# Versie_3.net
KiCad netlist of a schematic drawn in EAGLE
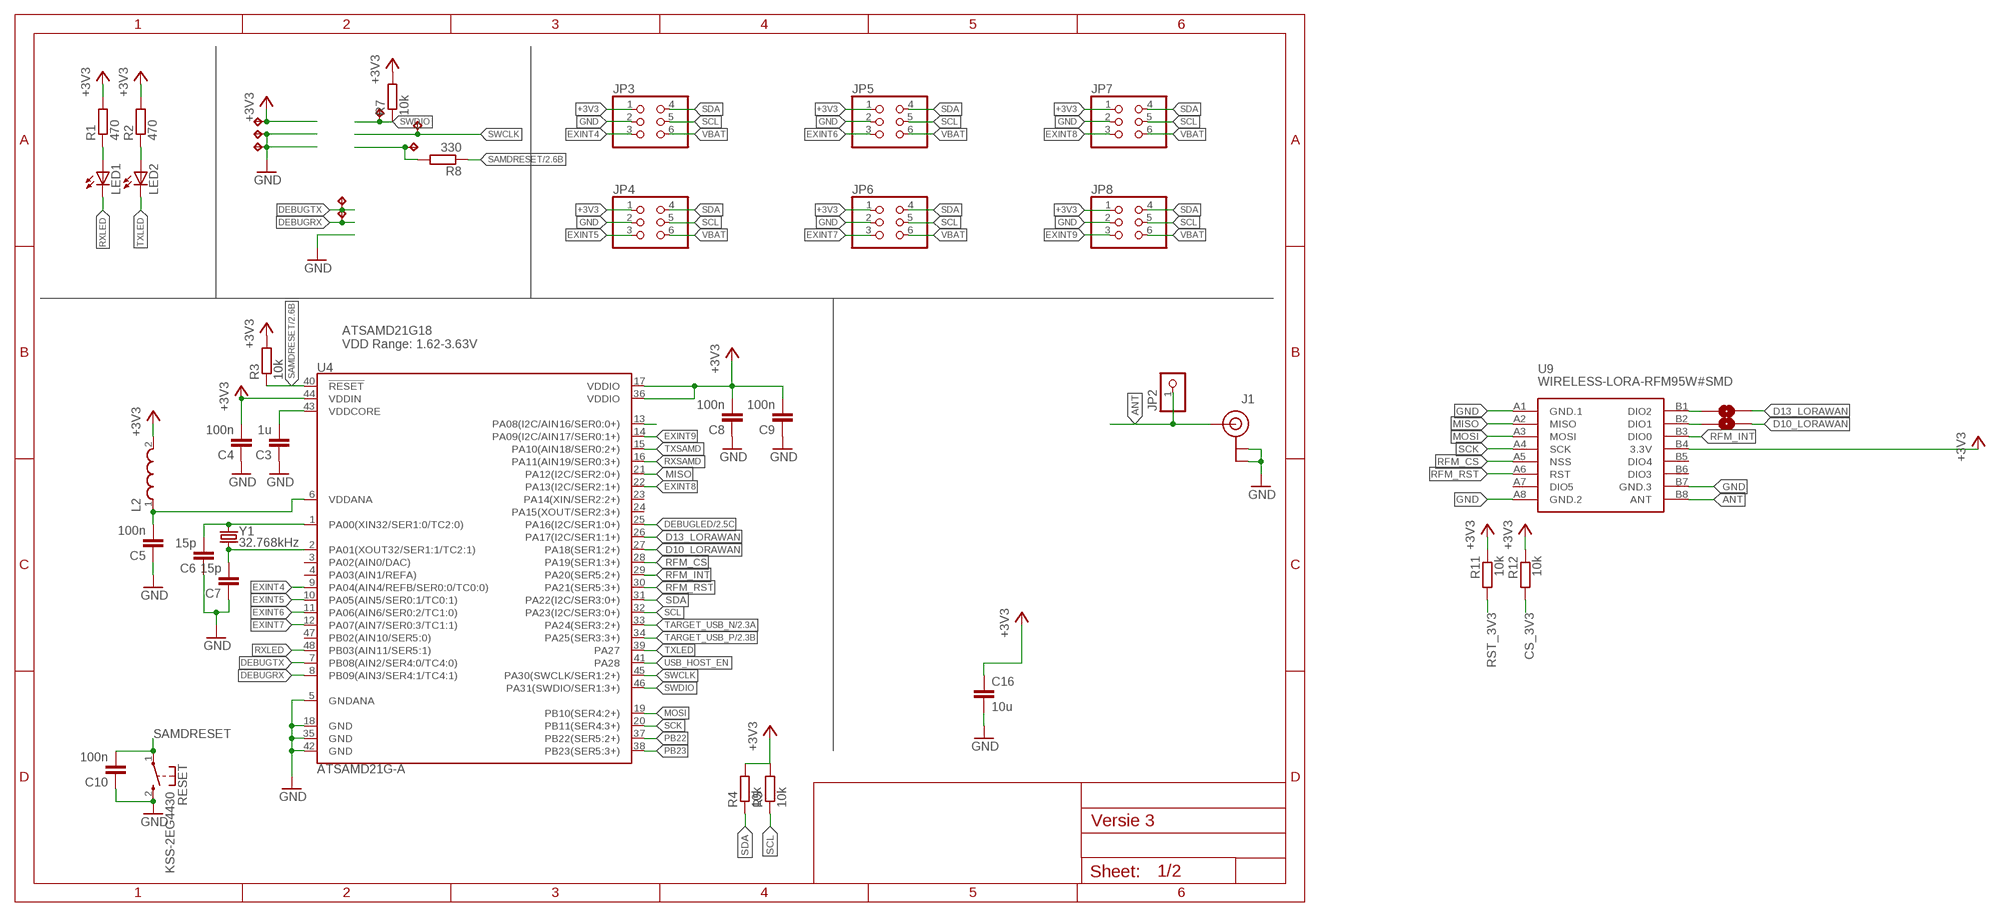
[diagram p0: schematic, sheet 1]
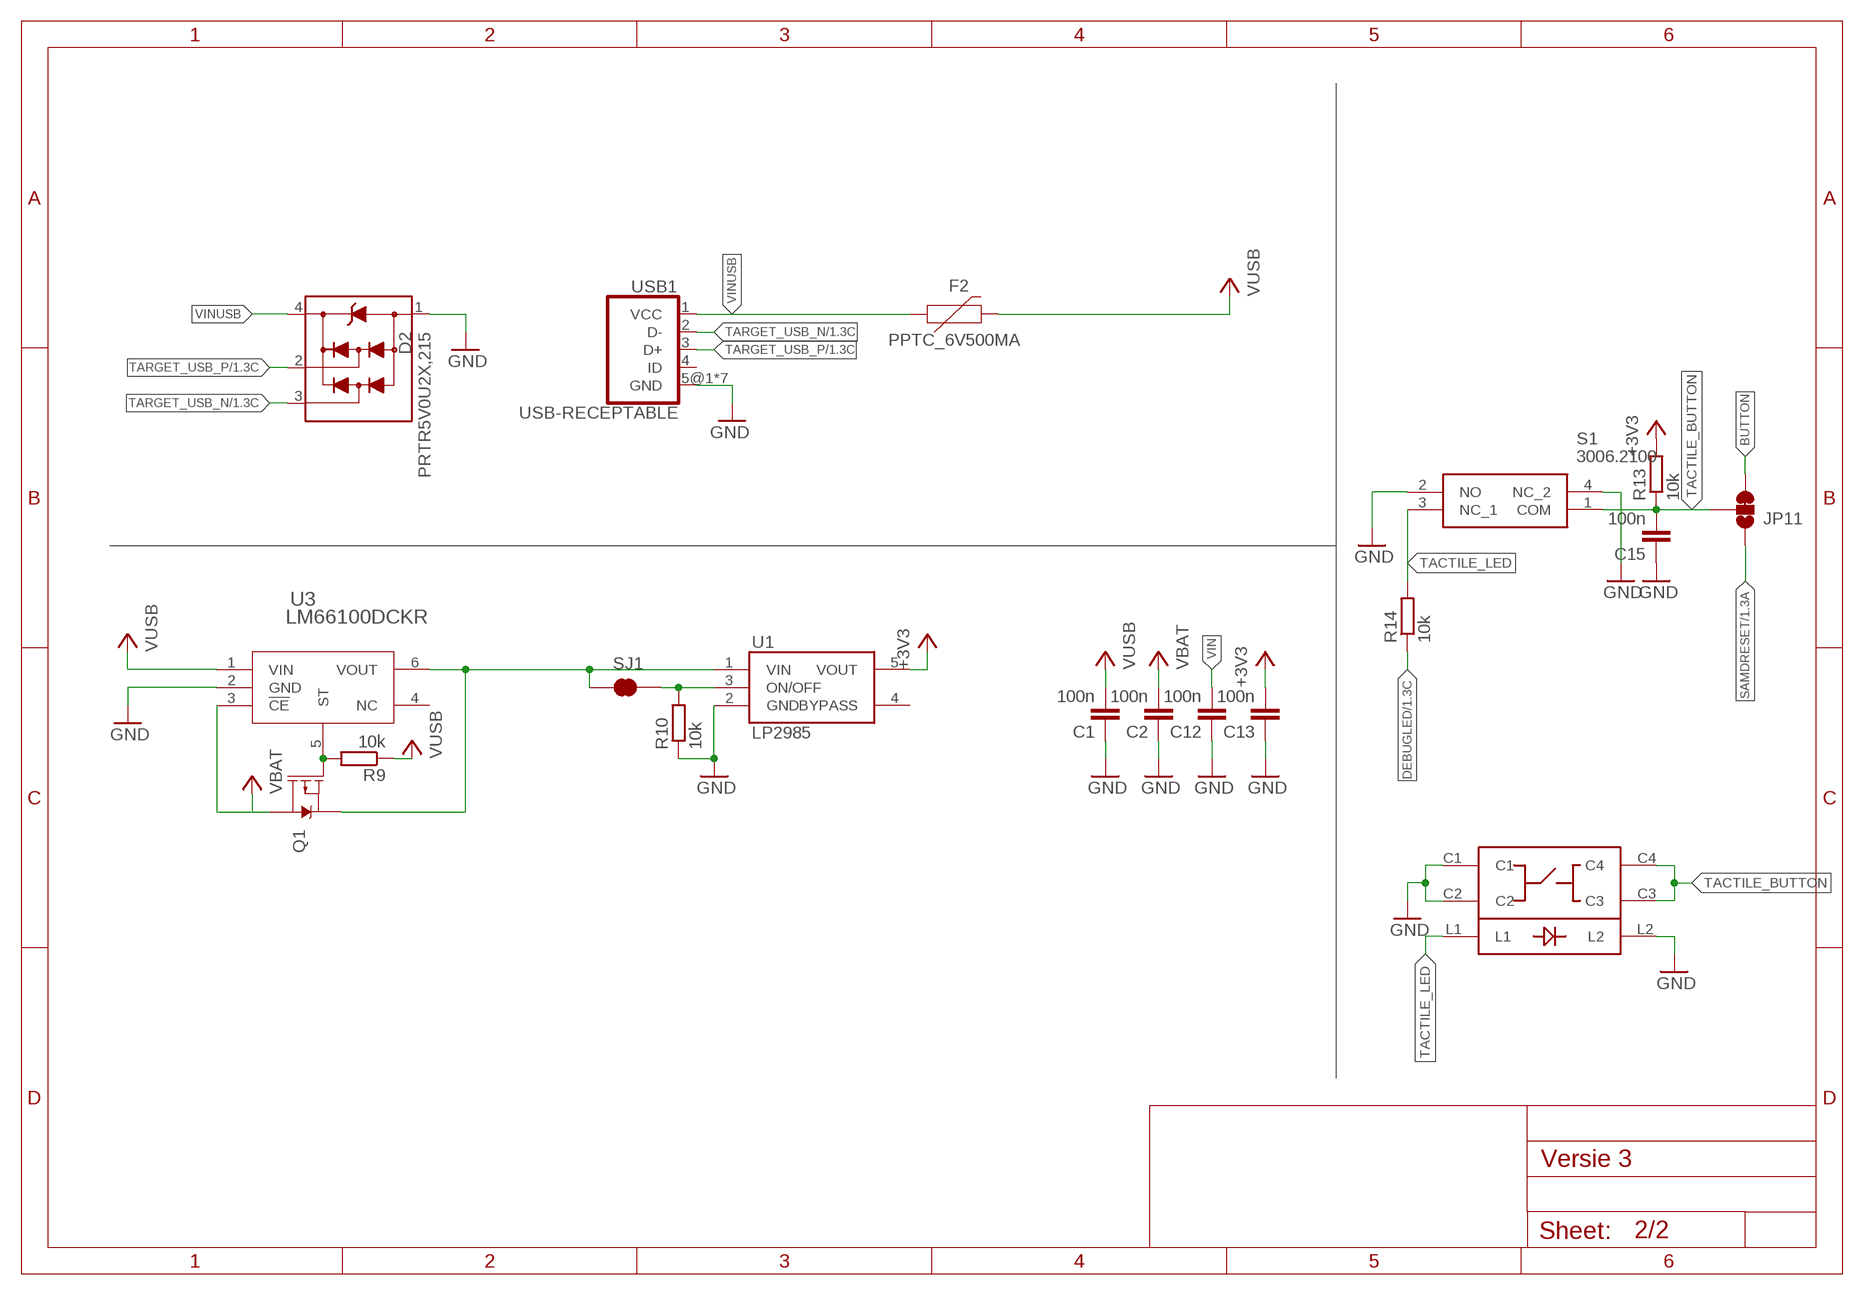
[diagram p1: schematic, sheet 2]

(export (version "E")
  (design (tool "Eeschema 10.0.6"))
  (components
    (comp (ref "C3")
      (value "1u")
      (footprint "eagle-import:C0603")
      (libsource (lib "eagle-import") (part "C-EUC0603"))
    )
    (comp (ref "C4")
      (value "100n")
      (footprint "eagle-import:C0603")
      (libsource (lib "eagle-import") (part "C-EUC0603"))
    )
    (comp (ref "C5")
      (value "100n")
      (footprint "eagle-import:C0603")
      (libsource (lib "eagle-import") (part "C-EUC0603"))
    )
    (comp (ref "C6")
      (value "15p")
      (footprint "eagle-import:C0603")
      (libsource (lib "eagle-import") (part "C-EUC0603"))
    )
    (comp (ref "C7")
      (value "15p")
      (footprint "eagle-import:C0603")
      (libsource (lib "eagle-import") (part "C-EUC0603"))
    )
    (comp (ref "C8")
      (value "100n")
      (footprint "eagle-import:C0603")
      (libsource (lib "eagle-import") (part "C-EUC0603"))
    )
    (comp (ref "C9")
      (value "100n")
      (footprint "eagle-import:C0603")
      (libsource (lib "eagle-import") (part "C-EUC0603"))
    )
    (comp (ref "C10")
      (value "100n")
      (footprint "eagle-import:C0603")
      (libsource (lib "eagle-import") (part "C-EUC0603"))
    )
    (comp (ref "C16")
      (value "10u")
      (footprint "eagle-import:C0603")
      (libsource (lib "eagle-import") (part "C-EUC0603"))
    )
    (comp (ref "J1")
      (value "U.FL")
      (footprint "eagle-import:U.FL")
      (libsource (lib "eagle-import") (part "U.FL"))
    )
    (comp (ref "JP2")
      (value "PINHD-1X1")
      (footprint "eagle-import:1X01")
      (libsource (lib "eagle-import") (part "PINHD-1X1"))
    )
    (comp (ref "JP3")
      (value "PINHD-2X3")
      (footprint "eagle-import:2X03")
      (libsource (lib "eagle-import") (part "PINHD-2X3"))
    )
    (comp (ref "JP4")
      (value "PINHD-2X3")
      (footprint "eagle-import:2X03")
      (libsource (lib "eagle-import") (part "PINHD-2X3"))
    )
    (comp (ref "JP5")
      (value "PINHD-2X3")
      (footprint "eagle-import:2X03")
      (libsource (lib "eagle-import") (part "PINHD-2X3"))
    )
    (comp (ref "JP6")
      (value "PINHD-2X3")
      (footprint "eagle-import:2X03")
      (libsource (lib "eagle-import") (part "PINHD-2X3"))
    )
    (comp (ref "JP7")
      (value "PINHD-2X3")
      (footprint "eagle-import:2X03")
      (libsource (lib "eagle-import") (part "PINHD-2X3"))
    )
    (comp (ref "JP8")
      (value "PINHD-2X3")
      (footprint "eagle-import:2X03")
      (libsource (lib "eagle-import") (part "PINHD-2X3"))
    )
    (comp (ref "JP9")
      (value "JUMPER-SMT_2_NO_NO-SILK")
      (footprint "eagle-import:SMT-JUMPER_2_NO_NO-SILK")
      (libsource (lib "eagle-import") (part "JUMPER-SMT_2_NO_NO-SILK"))
    )
    (comp (ref "JP10")
      (value "JUMPER-SMT_2_NO_NO-SILK")
      (footprint "eagle-import:SMT-JUMPER_2_NO_NO-SILK")
      (libsource (lib "eagle-import") (part "JUMPER-SMT_2_NO_NO-SILK"))
    )
    (comp (ref "L2")
      (value "WE-CBA_0603(WB/HS)")
      (footprint "eagle-import:WE-CBA_0603(W=2.2)")
      (libsource (lib "eagle-import") (part "WE-CBA_0603(WB/HS)"))
    )
    (comp (ref "LED1")
      (value "LEDCHIP-LED0603")
      (footprint "eagle-import:CHIP-LED0603")
      (libsource (lib "eagle-import") (part "LEDCHIP-LED0603"))
    )
    (comp (ref "LED2")
      (value "LEDCHIP-LED0603")
      (footprint "eagle-import:CHIP-LED0603")
      (libsource (lib "eagle-import") (part "LEDCHIP-LED0603"))
    )
    (comp (ref "R1")
      (value "470")
      (footprint "eagle-import:R0603")
      (libsource (lib "eagle-import") (part "R-EU_R0603"))
    )
    (comp (ref "R2")
      (value "470")
      (footprint "eagle-import:R0603")
      (libsource (lib "eagle-import") (part "R-EU_R0603"))
    )
    (comp (ref "R3")
      (value "10k")
      (footprint "eagle-import:R0603")
      (libsource (lib "eagle-import") (part "R-EU_R0603"))
    )
    (comp (ref "R4")
      (value "10k")
      (footprint "eagle-import:R0603")
      (libsource (lib "eagle-import") (part "R-EU_R0603"))
    )
    (comp (ref "R5")
      (value "10k")
      (footprint "eagle-import:R0603")
      (libsource (lib "eagle-import") (part "R-EU_R0603"))
    )
    (comp (ref "R7")
      (value "10k")
      (footprint "eagle-import:R0603")
      (libsource (lib "eagle-import") (part "R-EU_R0603"))
    )
    (comp (ref "R8")
      (value "330")
      (footprint "eagle-import:R0603")
      (libsource (lib "eagle-import") (part "R-EU_R0603"))
    )
    (comp (ref "R11")
      (value "10k")
      (footprint "eagle-import:0204_7")
      (libsource (lib "eagle-import") (part "resistor_R-EU_0204/7"))
    )
    (comp (ref "R12")
      (value "10k")
      (footprint "eagle-import:0204_7")
      (libsource (lib "eagle-import") (part "resistor_R-EU_0204/7"))
    )
    (comp (ref "RESET")
      (value "KSS-2EG4430")
      (footprint "eagle-import:KSS-2EG4430")
      (libsource (lib "eagle-import") (part "KSS-2EG4430"))
    )
    (comp (ref "TP1")
      (value "TPB1,27")
      (footprint "eagle-import:B1,27")
      (libsource (lib "eagle-import") (part "TPB1,27"))
    )
    (comp (ref "TP2")
      (value "TPB1,27")
      (footprint "eagle-import:B1,27")
      (libsource (lib "eagle-import") (part "TPB1,27"))
    )
    (comp (ref "TP3")
      (value "TPB1,27")
      (footprint "eagle-import:B1,27")
      (libsource (lib "eagle-import") (part "TPB1,27"))
    )
    (comp (ref "TP4")
      (value "TPB1,27")
      (footprint "eagle-import:B1,27")
      (libsource (lib "eagle-import") (part "TPB1,27"))
    )
    (comp (ref "TP5")
      (value "TPB1,27")
      (footprint "eagle-import:B1,27")
      (libsource (lib "eagle-import") (part "TPB1,27"))
    )
    (comp (ref "TP6")
      (value "TPB1,27")
      (footprint "eagle-import:B1,27")
      (libsource (lib "eagle-import") (part "TPB1,27"))
    )
    (comp (ref "TP7")
      (value "TPB1,27")
      (footprint "eagle-import:B1,27")
      (libsource (lib "eagle-import") (part "TPB1,27"))
    )
    (comp (ref "TP8")
      (value "TPB1,27")
      (footprint "eagle-import:B1,27")
      (libsource (lib "eagle-import") (part "TPB1,27"))
    )
    (comp (ref "U4")
      (value "ATSAMD21G-A")
      (footprint "eagle-import:TQFP-48")
      (libsource (lib "eagle-import") (part "ATSAMD21G-A"))
    )
    (comp (ref "U9")
      (value "WIRELESS-LORA-RFM95W#SMD")
      (footprint "eagle-import:WIRELESS-LORA-RFM95W#SMD")
      (libsource (lib "eagle-import") (part "WIRELESS-LORA-RFM95W#SMD"))
    )
    (comp (ref "Y1")
      (value "32.768kHz")
      (footprint "eagle-import:CRYSTAL-SMD-3.2X1.5MM")
      (libsource (lib "eagle-import") (part "CRYSTAL3.2X1.5MM"))
    )
    (comp (ref "C1")
      (value "100n")
      (footprint "eagle-import:C0603")
      (libsource (lib "eagle-import") (part "C-EUC0603"))
    )
    (comp (ref "C2")
      (value "100n")
      (footprint "eagle-import:C0603")
      (libsource (lib "eagle-import") (part "C-EUC0603"))
    )
    (comp (ref "C12")
      (value "100n")
      (footprint "eagle-import:C0603")
      (libsource (lib "eagle-import") (part "C-EUC0603"))
    )
    (comp (ref "C13")
      (value "100n")
      (footprint "eagle-import:C0603")
      (libsource (lib "eagle-import") (part "C-EUC0603"))
    )
    (comp (ref "C15")
      (value "100n")
      (footprint "eagle-import:C0603")
      (libsource (lib "eagle-import") (part "C-EUC0603"))
    )
    (comp (ref "D2")
      (value "PRTR5V0U2X,215")
      (footprint "eagle-import:SOT143B")
      (fields (field (name "MF") "Nexperia USA Inc."))
      (libsource (lib "eagle-import") (part "PRTR5V0U2X,215"))
    )
    (comp (ref "F2")
      (value "PPTC_6V500MA")
      (footprint "eagle-import:0805")
      (libsource (lib "eagle-import") (part "PPTC_6V500MA"))
    )
    (comp (ref "JP11")
      (value "JUMPER-SMT_3_1-NC_TRACE_SILK")
      (footprint "eagle-import:SMT-JUMPER_3_1-NC_TRACE_SILK")
      (libsource (lib "eagle-import") (part "JUMPER-SMT_3_1-NC_TRACE_SILK"))
    )
    (comp (ref "Q1")
      (value "MOSFET_PCH-DMG2307L")
      (footprint "eagle-import:SOT23-3")
      (libsource (lib "eagle-import") (part "MOSFET_PCH-DMG2307L"))
    )
    (comp (ref "R9")
      (value "10k")
      (footprint "eagle-import:R0603")
      (libsource (lib "eagle-import") (part "R-EU_R0603"))
    )
    (comp (ref "R10")
      (value "10k")
      (footprint "eagle-import:R0603")
      (libsource (lib "eagle-import") (part "R-EU_R0603"))
    )
    (comp (ref "R13")
      (value "10k")
      (footprint "eagle-import:R0603")
      (libsource (lib "eagle-import") (part "R-EU_R0603"))
    )
    (comp (ref "R14")
      (value "10k")
      (footprint "eagle-import:R0603")
      (libsource (lib "eagle-import") (part "R-EU_R0603"))
    )
    (comp (ref "S1")
      (value "3006.2100")
      (footprint "eagle-import:30062101")
      (fields (field (name "MOUSER_PART_NUMBER") "979-3006.2100"))
      (libsource (lib "eagle-import") (part "3006.2100"))
    )
    (comp (ref "SJ1")
      (value "JUMPER-PAD-2-NC_BY_TRACENO_SILK")
      (footprint "eagle-import:PAD-JUMPER-2-NC_BY_TRACE_NO_SILK")
      (libsource (lib "eagle-import") (part "JUMPER-PAD-2-NC_BY_TRACENO_SILK"))
    )
    (comp (ref "U$1")
      (value "LS1201")
      (footprint "eagle-import:LS1201")
      (libsource (lib "eagle-import") (part "LS1201"))
    )
    (comp (ref "U1")
      (value "LP2985AIM5-3.3")
      (footprint "eagle-import:SOT25")
      (libsource (lib "eagle-import") (part "LP2985AIM5-3.3"))
    )
    (comp (ref "U3")
      (value "LM66100DCKR")
      (footprint "eagle-import:DCK6_TEX")
      (fields (field (name "COPYRIGHT") "Copyright (C) 2018 Accelerated Designs. All rights reserved"))
      (libsource (lib "eagle-import") (part "LM66100DCKR"))
    )
    (comp (ref "USB1")
      (value "USB-RECEPTABLE")
      (footprint "eagle-import:FCI-10103594-0001LF")
      (libsource (lib "eagle-import") (part "USB-RECEPTABLE"))
    )
  )
  (nets
    (net (code "1") (name "+3V3") (class "Default")
      (node (ref "C13") (pin "2") (pinfunction "2_2") (pintype "passive"))
      (node (ref "C16") (pin "1") (pinfunction "1_1") (pintype "passive"))
      (node (ref "C4") (pin "2") (pinfunction "2_2") (pintype "passive"))
      (node (ref "C8") (pin "2") (pinfunction "2_2") (pintype "passive"))
      (node (ref "C9") (pin "2") (pinfunction "2_2") (pintype "passive"))
      (node (ref "JP3") (pin "1") (pinfunction "1_1") (pintype "passive"))
      (node (ref "JP4") (pin "1") (pinfunction "1_1") (pintype "passive"))
      (node (ref "JP5") (pin "1") (pinfunction "1_1") (pintype "passive"))
      (node (ref "JP6") (pin "1") (pinfunction "1_1") (pintype "passive"))
      (node (ref "JP7") (pin "1") (pinfunction "1_1") (pintype "passive"))
      (node (ref "JP8") (pin "1") (pinfunction "1_1") (pintype "passive"))
      (node (ref "L2") (pin "2") (pinfunction "2_2") (pintype "passive"))
      (node (ref "R1") (pin "2") (pinfunction "2_2") (pintype "passive"))
      (node (ref "R11") (pin "1") (pinfunction "1_1") (pintype "passive"))
      (node (ref "R12") (pin "1") (pinfunction "1_1") (pintype "passive"))
      (node (ref "R13") (pin "2") (pinfunction "2_2") (pintype "passive"))
      (node (ref "R2") (pin "2") (pinfunction "2_2") (pintype "passive"))
      (node (ref "R3") (pin "2") (pinfunction "2_2") (pintype "passive"))
      (node (ref "R4") (pin "2") (pinfunction "2_2") (pintype "passive"))
      (node (ref "R5") (pin "2") (pinfunction "2_2") (pintype "passive"))
      (node (ref "R7") (pin "2") (pinfunction "2_2") (pintype "passive"))
      (node (ref "TP1") (pin "TP") (pinfunction "TP_TP") (pintype "input"))
      (node (ref "U1") (pin "5") (pinfunction "VOUT_5") (pintype "power_in"))
      (node (ref "U4") (pin "17") (pinfunction "VDDIO_17") (pintype "bidirectional"))
      (node (ref "U4") (pin "36") (pinfunction "VDDIO_36") (pintype "bidirectional"))
      (node (ref "U4") (pin "44") (pinfunction "VDDIN_44") (pintype "bidirectional"))
      (node (ref "U9") (pin "B4") (pinfunction "3.3V_B4") (pintype "power_in"))
    )
    (net (code "2") (name "ANT") (class "Default")
      (node (ref "J1") (pin "P$3") (pinfunction "SIGNAL_P$3") (pintype "bidirectional"))
      (node (ref "JP2") (pin "1") (pinfunction "1_1") (pintype "passive"))
      (node (ref "U9") (pin "B8") (pinfunction "ANT_B8") (pintype "passive"))
    )
    (net (code "3") (name "BUTTON") (class "Default")
      (node (ref "JP11") (pin "3") (pinfunction "3_3") (pintype "passive"))
      (node (ref "U4") (pin "13") (pinfunction "PA08(I2C/AIN16/SER0:0+)_13") (pintype "bidirectional"))
    )
    (net (code "4") (name "BYPASS") (class "Default")
      (node (ref "U1") (pin "4") (pinfunction "BYPASS_4") (pintype "power_in"))
    )
    (net (code "5") (name "CS_3V3") (class "Default")
      (node (ref "R12") (pin "2") (pinfunction "2_2") (pintype "passive"))
    )
    (net (code "6") (name "D10_LORAWAN") (class "Default")
      (node (ref "JP10") (pin "2") (pinfunction "2_2") (pintype "passive"))
      (node (ref "U4") (pin "27") (pinfunction "PA18(SER1:2+)_27") (pintype "bidirectional"))
    )
    (net (code "7") (name "D13_LORAWAN") (class "Default")
      (node (ref "JP9") (pin "2") (pinfunction "2_2") (pintype "passive"))
      (node (ref "U4") (pin "26") (pinfunction "PA17(I2C/SER1:1+)_26") (pintype "bidirectional"))
    )
    (net (code "8") (name "DEBUGLED") (class "Default")
      (node (ref "R14") (pin "1") (pinfunction "1_1") (pintype "passive"))
      (node (ref "U4") (pin "25") (pinfunction "PA16(I2C/SER1:0+)_25") (pintype "bidirectional"))
    )
    (net (code "9") (name "DEBUGRX") (class "Default")
      (node (ref "TP8") (pin "TP") (pinfunction "TP_TP") (pintype "input"))
      (node (ref "U4") (pin "8") (pinfunction "PB09(AIN3/SER4:1/TC4:1)_8") (pintype "bidirectional"))
    )
    (net (code "10") (name "DEBUGTX") (class "Default")
      (node (ref "TP7") (pin "TP") (pinfunction "TP_TP") (pintype "input"))
      (node (ref "U4") (pin "7") (pinfunction "PB08(AIN2/SER4:0/TC4:0)_7") (pintype "bidirectional"))
    )
    (net (code "11") (name "EXINT4") (class "Default")
      (node (ref "JP3") (pin "3") (pinfunction "3_3") (pintype "passive"))
      (node (ref "U4") (pin "9") (pinfunction "PA04(AIN4/REFB/SER0:0/TC0:0)_9") (pintype "bidirectional"))
    )
    (net (code "12") (name "EXINT5") (class "Default")
      (node (ref "JP4") (pin "3") (pinfunction "3_3") (pintype "passive"))
      (node (ref "U4") (pin "10") (pinfunction "PA05(AIN5/SER0:1/TC0:1)_10") (pintype "bidirectional"))
    )
    (net (code "13") (name "EXINT6") (class "Default")
      (node (ref "JP5") (pin "3") (pinfunction "3_3") (pintype "passive"))
      (node (ref "U4") (pin "11") (pinfunction "PA06(AIN6/SER0:2/TC1:0)_11") (pintype "bidirectional"))
    )
    (net (code "14") (name "EXINT7") (class "Default")
      (node (ref "JP6") (pin "3") (pinfunction "3_3") (pintype "passive"))
      (node (ref "U4") (pin "12") (pinfunction "PA07(AIN7/SER0:3/TC1:1)_12") (pintype "bidirectional"))
    )
    (net (code "15") (name "EXINT8") (class "Default")
      (node (ref "JP7") (pin "3") (pinfunction "3_3") (pintype "passive"))
      (node (ref "U4") (pin "22") (pinfunction "PA13(I2C/SER2:1+)_22") (pintype "bidirectional"))
    )
    (net (code "16") (name "EXINT9") (class "Default")
      (node (ref "JP8") (pin "3") (pinfunction "3_3") (pintype "passive"))
      (node (ref "U4") (pin "14") (pinfunction "PA09(I2C/AIN17/SER0:1+)_14") (pintype "bidirectional"))
    )
    (net (code "17") (name "GND") (class "Default")
      (node (ref "C1") (pin "1") (pinfunction "1_1") (pintype "passive"))
      (node (ref "C10") (pin "1") (pinfunction "1_1") (pintype "passive"))
      (node (ref "C12") (pin "1") (pinfunction "1_1") (pintype "passive"))
      (node (ref "C13") (pin "1") (pinfunction "1_1") (pintype "passive"))
      (node (ref "C15") (pin "1") (pinfunction "1_1") (pintype "passive"))
      (node (ref "C16") (pin "2") (pinfunction "2_2") (pintype "passive"))
      (node (ref "C2") (pin "1") (pinfunction "1_1") (pintype "passive"))
      (node (ref "C3") (pin "1") (pinfunction "1_1") (pintype "passive"))
      (node (ref "C4") (pin "1") (pinfunction "1_1") (pintype "passive"))
      (node (ref "C5") (pin "1") (pinfunction "1_1") (pintype "passive"))
      (node (ref "C6") (pin "1") (pinfunction "1_1") (pintype "passive"))
      (node (ref "C7") (pin "1") (pinfunction "1_1") (pintype "passive"))
      (node (ref "C8") (pin "1") (pinfunction "1_1") (pintype "passive"))
      (node (ref "C9") (pin "1") (pinfunction "1_1") (pintype "passive"))
      (node (ref "D2") (pin "1") (pinfunction "P$1_1") (pintype "passive"))
      (node (ref "J1") (pin "P$1") (pinfunction "GND_P$1") (pintype "bidirectional"))
      (node (ref "J1") (pin "P$2") (pinfunction "GND_P$2") (pintype "bidirectional"))
      (node (ref "JP3") (pin "2") (pinfunction "2_2") (pintype "passive"))
      (node (ref "JP4") (pin "2") (pinfunction "2_2") (pintype "passive"))
      (node (ref "JP5") (pin "2") (pinfunction "2_2") (pintype "passive"))
      (node (ref "JP6") (pin "2") (pinfunction "2_2") (pintype "passive"))
      (node (ref "JP7") (pin "2") (pinfunction "2_2") (pintype "passive"))
      (node (ref "JP8") (pin "2") (pinfunction "2_2") (pintype "passive"))
      (node (ref "R10") (pin "1") (pinfunction "1_1") (pintype "passive"))
      (node (ref "RESET") (pin "2") (pinfunction "S_2") (pintype "passive"))
      (node (ref "S1") (pin "2") (pinfunction "NO_2") (pintype "bidirectional"))
      (node (ref "S1") (pin "4") (pinfunction "NC_2_4") (pintype "bidirectional"))
      (node (ref "TP2") (pin "TP") (pinfunction "TP_TP") (pintype "input"))
      (node (ref "TP3") (pin "TP") (pinfunction "TP_TP") (pintype "input"))
      (node (ref "U$1") (pin "C1") (pinfunction "C1_C1") (pintype "bidirectional"))
      (node (ref "U$1") (pin "C2") (pinfunction "C2_C2") (pintype "bidirectional"))
      (node (ref "U$1") (pin "L2") (pinfunction "L2_L2") (pintype "bidirectional"))
      (node (ref "U1") (pin "2") (pinfunction "GND_2") (pintype "power_in"))
      (node (ref "U3") (pin "2") (pinfunction "GND_2") (pintype "power_in"))
      (node (ref "U4") (pin "18") (pinfunction "GND_18") (pintype "bidirectional"))
      (node (ref "U4") (pin "35") (pinfunction "GND_35") (pintype "bidirectional"))
      (node (ref "U4") (pin "42") (pinfunction "GND_42") (pintype "bidirectional"))
      (node (ref "U4") (pin "5") (pinfunction "GNDANA_5") (pintype "bidirectional"))
      (node (ref "U9") (pin "A1") (pinfunction "GND.1_A1") (pintype "power_in"))
      (node (ref "U9") (pin "A8") (pinfunction "GND.2_A8") (pintype "power_in"))
      (node (ref "U9") (pin "B7") (pinfunction "GND.3_B7") (pintype "power_in"))
      (node (ref "USB1") (pin "5@1") (pinfunction "GND_5@1") (pintype "bidirectional"))
      (node (ref "USB1") (pin "5@2") (pinfunction "GND_5@2") (pintype "bidirectional"))
      (node (ref "USB1") (pin "5@3") (pinfunction "GND_5@3") (pintype "bidirectional"))
      (node (ref "USB1") (pin "5@4") (pinfunction "GND_5@4") (pintype "bidirectional"))
      (node (ref "USB1") (pin "5@5") (pinfunction "GND_5@5") (pintype "bidirectional"))
      (node (ref "USB1") (pin "5@6") (pinfunction "GND_5@6") (pintype "bidirectional"))
      (node (ref "USB1") (pin "5@7") (pinfunction "GND_5@7") (pintype "bidirectional"))
    )
    (net (code "18") (name "MISO") (class "Default")
      (node (ref "U4") (pin "21") (pinfunction "PA12(I2C/SER2:0+)_21") (pintype "bidirectional"))
      (node (ref "U9") (pin "A2") (pinfunction "MISO_A2") (pintype "bidirectional"))
    )
    (net (code "19") (name "MOSI") (class "Default")
      (node (ref "U4") (pin "19") (pinfunction "PB10(SER4:2+)_19") (pintype "bidirectional"))
      (node (ref "U9") (pin "A3") (pinfunction "MOSI_A3") (pintype "bidirectional"))
    )
    (net (code "20") (name "Net-(LED1-PadA)") (class "Default")
      (node (ref "LED1") (pin "A") (pinfunction "A_A") (pintype "passive"))
      (node (ref "R1") (pin "1") (pinfunction "1_1") (pintype "passive"))
    )
    (net (code "21") (name "Net-(LED2-PadA)") (class "Default")
      (node (ref "LED2") (pin "A") (pinfunction "A_A") (pintype "passive"))
      (node (ref "R2") (pin "1") (pinfunction "1_1") (pintype "passive"))
    )
    (net (code "22") (name "Net-(Q1-G)") (class "Default")
      (node (ref "Q1") (pin "1") (pinfunction "G_1") (pintype "bidirectional"))
      (node (ref "R9") (pin "2") (pinfunction "2_2") (pintype "passive"))
      (node (ref "U3") (pin "5") (pinfunction "ST_5") (pintype "output"))
    )
    (net (code "23") (name "Net-(R8-Pad2)") (class "Default")
      (node (ref "R8") (pin "2") (pinfunction "2_2") (pintype "passive"))
      (node (ref "TP6") (pin "TP") (pinfunction "TP_TP") (pintype "input"))
    )
    (net (code "24") (name "Net-(U1-ON{slash}OFF)") (class "Default")
      (node (ref "R10") (pin "2") (pinfunction "2_2") (pintype "passive"))
      (node (ref "SJ1") (pin "1") (pinfunction "1_1") (pintype "passive"))
      (node (ref "U1") (pin "3") (pinfunction "ON/OFF_3") (pintype "input"))
    )
    (net (code "25") (name "Net-(U4-PA00(XIN32{slash}SER1:0{slash}TC2:0))") (class "Default")
      (node (ref "C6") (pin "2") (pinfunction "2_2") (pintype "passive"))
      (node (ref "U4") (pin "1") (pinfunction "PA00(XIN32/SER1:0/TC2:0)_1") (pintype "bidirectional"))
      (node (ref "Y1") (pin "P$2") (pinfunction "2_P$2") (pintype "passive"))
    )
    (net (code "26") (name "Net-(U4-PA01(XOUT32{slash}SER1:1{slash}TC2:1))") (class "Default")
      (node (ref "C7") (pin "2") (pinfunction "2_2") (pintype "passive"))
      (node (ref "U4") (pin "2") (pinfunction "PA01(XOUT32/SER1:1/TC2:1)_2") (pintype "bidirectional"))
      (node (ref "Y1") (pin "P$1") (pinfunction "1_P$1") (pintype "passive"))
    )
    (net (code "27") (name "Net-(U4-VDDANA)") (class "Default")
      (node (ref "C5") (pin "2") (pinfunction "2_2") (pintype "passive"))
      (node (ref "L2") (pin "1") (pinfunction "1_1") (pintype "passive"))
      (node (ref "U4") (pin "6") (pinfunction "VDDANA_6") (pintype "bidirectional"))
    )
    (net (code "28") (name "Net-(U4-VDDCORE)") (class "Default")
      (node (ref "C3") (pin "2") (pinfunction "2_2") (pintype "passive"))
      (node (ref "U4") (pin "43") (pinfunction "VDDCORE_43") (pintype "bidirectional"))
    )
    (net (code "29") (name "Net-(U9-DIO1)") (class "Default")
      (node (ref "JP10") (pin "1") (pinfunction "1_1") (pintype "passive"))
      (node (ref "U9") (pin "B2") (pinfunction "DIO1_B2") (pintype "bidirectional"))
    )
    (net (code "30") (name "Net-(U9-DIO2)") (class "Default")
      (node (ref "JP9") (pin "1") (pinfunction "1_1") (pintype "passive"))
      (node (ref "U9") (pin "B1") (pinfunction "DIO2_B1") (pintype "bidirectional"))
    )
    (net (code "31") (name "PB22") (class "Default")
      (node (ref "U4") (pin "37") (pinfunction "PB22(SER5:2+)_37") (pintype "bidirectional"))
    )
    (net (code "32") (name "PB23") (class "Default")
      (node (ref "U4") (pin "38") (pinfunction "PB23(SER5:3+)_38") (pintype "bidirectional"))
    )
    (net (code "33") (name "RFM_CS") (class "Default")
      (node (ref "U4") (pin "28") (pinfunction "PA19(SER1:3+)_28") (pintype "bidirectional"))
      (node (ref "U9") (pin "A5") (pinfunction "NSS_A5") (pintype "bidirectional"))
    )
    (net (code "34") (name "RFM_INT") (class "Default")
      (node (ref "U4") (pin "29") (pinfunction "PA20(SER5:2+)_29") (pintype "bidirectional"))
      (node (ref "U9") (pin "B3") (pinfunction "DIO0_B3") (pintype "bidirectional"))
    )
    (net (code "35") (name "RFM_RST") (class "Default")
      (node (ref "U4") (pin "30") (pinfunction "PA21(SER5:3+)_30") (pintype "bidirectional"))
      (node (ref "U9") (pin "A6") (pinfunction "RST_A6") (pintype "bidirectional"))
    )
    (net (code "36") (name "RST_3V3") (class "Default")
      (node (ref "R11") (pin "2") (pinfunction "2_2") (pintype "passive"))
    )
    (net (code "37") (name "RXLED") (class "Default")
      (node (ref "LED1") (pin "C") (pinfunction "C_C") (pintype "passive"))
      (node (ref "U4") (pin "48") (pinfunction "PB03(AIN11/SER5:1)_48") (pintype "bidirectional"))
    )
    (net (code "38") (name "RXSAMD") (class "Default")
      (node (ref "U4") (pin "16") (pinfunction "PA11(AIN19/SER0:3+)_16") (pintype "bidirectional"))
    )
    (net (code "39") (name "SAMDRESET") (class "Default")
      (node (ref "C10") (pin "2") (pinfunction "2_2") (pintype "passive"))
      (node (ref "JP11") (pin "1") (pinfunction "1_1") (pintype "passive"))
      (node (ref "R3") (pin "1") (pinfunction "1_1") (pintype "passive"))
      (node (ref "R8") (pin "1") (pinfunction "1_1") (pintype "passive"))
      (node (ref "RESET") (pin "1") (pinfunction "P_1") (pintype "passive"))
      (node (ref "U4") (pin "40") (pinfunction "~{RESET}_40") (pintype "bidirectional"))
    )
    (net (code "40") (name "SCK") (class "Default")
      (node (ref "U4") (pin "20") (pinfunction "PB11(SER4:3+)_20") (pintype "bidirectional"))
      (node (ref "U9") (pin "A4") (pinfunction "SCK_A4") (pintype "bidirectional"))
    )
    (net (code "41") (name "SCL") (class "Default")
      (node (ref "JP3") (pin "5") (pinfunction "5_5") (pintype "passive"))
      (node (ref "JP4") (pin "5") (pinfunction "5_5") (pintype "passive"))
      (node (ref "JP5") (pin "5") (pinfunction "5_5") (pintype "passive"))
      (node (ref "JP6") (pin "5") (pinfunction "5_5") (pintype "passive"))
      (node (ref "JP7") (pin "5") (pinfunction "5_5") (pintype "passive"))
      (node (ref "JP8") (pin "5") (pinfunction "5_5") (pintype "passive"))
      (node (ref "R5") (pin "1") (pinfunction "1_1") (pintype "passive"))
      (node (ref "U4") (pin "32") (pinfunction "PA23(I2C/SER3:0+)_32") (pintype "bidirectional"))
    )
    (net (code "42") (name "SDA") (class "Default")
      (node (ref "JP3") (pin "4") (pinfunction "4_4") (pintype "passive"))
      (node (ref "JP4") (pin "4") (pinfunction "4_4") (pintype "passive"))
      (node (ref "JP5") (pin "4") (pinfunction "4_4") (pintype "passive"))
      (node (ref "JP6") (pin "4") (pinfunction "4_4") (pintype "passive"))
      (node (ref "JP7") (pin "4") (pinfunction "4_4") (pintype "passive"))
      (node (ref "JP8") (pin "4") (pinfunction "4_4") (pintype "passive"))
      (node (ref "R4") (pin "1") (pinfunction "1_1") (pintype "passive"))
      (node (ref "U4") (pin "31") (pinfunction "PA22(I2C/SER3:0+)_31") (pintype "bidirectional"))
    )
    (net (code "43") (name "SWCLK") (class "Default")
      (node (ref "TP5") (pin "TP") (pinfunction "TP_TP") (pintype "input"))
      (node (ref "U4") (pin "45") (pinfunction "PA30(SWCLK/SER1:2+)_45") (pintype "bidirectional"))
    )
    (net (code "44") (name "SWDIO") (class "Default")
      (node (ref "R7") (pin "1") (pinfunction "1_1") (pintype "passive"))
      (node (ref "TP4") (pin "TP") (pinfunction "TP_TP") (pintype "input"))
      (node (ref "U4") (pin "46") (pinfunction "PA31(SWDIO/SER1:3+)_46") (pintype "bidirectional"))
    )
    (net (code "45") (name "TACTILE_BUTTON") (class "Default")
      (node (ref "C15") (pin "2") (pinfunction "2_2") (pintype "passive"))
      (node (ref "JP11") (pin "2") (pinfunction "2_2") (pintype "passive"))
      (node (ref "R13") (pin "1") (pinfunction "1_1") (pintype "passive"))
      (node (ref "S1") (pin "1") (pinfunction "COM_1") (pintype "bidirectional"))
      (node (ref "U$1") (pin "C3") (pinfunction "C3_C3") (pintype "bidirectional"))
      (node (ref "U$1") (pin "C4") (pinfunction "C4_C4") (pintype "bidirectional"))
    )
    (net (code "46") (name "TACTILE_LED") (class "Default")
      (node (ref "R14") (pin "2") (pinfunction "2_2") (pintype "passive"))
      (node (ref "S1") (pin "3") (pinfunction "NC_1_3") (pintype "bidirectional"))
      (node (ref "U$1") (pin "L1") (pinfunction "L1_L1") (pintype "bidirectional"))
    )
    (net (code "47") (name "TARGET_USB_N") (class "Default")
      (node (ref "D2") (pin "3") (pinfunction "P$3_3") (pintype "passive"))
      (node (ref "U4") (pin "33") (pinfunction "PA24(SER3:2+)_33") (pintype "bidirectional"))
      (node (ref "USB1") (pin "2") (pinfunction "D-_2") (pintype "bidirectional"))
    )
    (net (code "48") (name "TARGET_USB_P") (class "Default")
      (node (ref "D2") (pin "2") (pinfunction "P$2_2") (pintype "passive"))
      (node (ref "U4") (pin "34") (pinfunction "PA25(SER3:3+)_34") (pintype "bidirectional"))
      (node (ref "USB1") (pin "3") (pinfunction "D+_3") (pintype "bidirectional"))
    )
    (net (code "49") (name "TXLED") (class "Default")
      (node (ref "LED2") (pin "C") (pinfunction "C_C") (pintype "passive"))
      (node (ref "U4") (pin "39") (pinfunction "PA27_39") (pintype "bidirectional"))
    )
    (net (code "50") (name "TXSAMD") (class "Default")
      (node (ref "U4") (pin "15") (pinfunction "PA10(AIN18/SER0:2+)_15") (pintype "bidirectional"))
    )
    (net (code "51") (name "USB_HOST_EN") (class "Default")
      (node (ref "U4") (pin "41") (pinfunction "PA28_41") (pintype "bidirectional"))
    )
    (net (code "52") (name "VBAT") (class "Default")
      (node (ref "C2") (pin "2") (pinfunction "2_2") (pintype "passive"))
      (node (ref "JP3") (pin "6") (pinfunction "6_6") (pintype "passive"))
      (node (ref "JP4") (pin "6") (pinfunction "6_6") (pintype "passive"))
      (node (ref "JP5") (pin "6") (pinfunction "6_6") (pintype "passive"))
      (node (ref "JP6") (pin "6") (pinfunction "6_6") (pintype "passive"))
      (node (ref "JP7") (pin "6") (pinfunction "6_6") (pintype "passive"))
      (node (ref "JP8") (pin "6") (pinfunction "6_6") (pintype "passive"))
      (node (ref "Q1") (pin "3") (pinfunction "D_3") (pintype "bidirectional"))
      (node (ref "U3") (pin "3") (pinfunction "~{CE}_3") (pintype "input"))
    )
    (net (code "53") (name "VIN") (class "Default")
      (node (ref "C12") (pin "2") (pinfunction "2_2") (pintype "passive"))
      (node (ref "Q1") (pin "2") (pinfunction "S_2") (pintype "bidirectional"))
      (node (ref "SJ1") (pin "2") (pinfunction "2_2") (pintype "passive"))
      (node (ref "U1") (pin "1") (pinfunction "VIN_1") (pintype "power_in"))
      (node (ref "U3") (pin "6") (pinfunction "VOUT_6") (pintype "output"))
    )
    (net (code "54") (name "VINUSB") (class "Default")
      (node (ref "D2") (pin "4") (pinfunction "P$4_4") (pintype "passive"))
      (node (ref "F2") (pin "1") (pinfunction "1_1") (pintype "bidirectional"))
      (node (ref "USB1") (pin "1") (pinfunction "VCC_1") (pintype "bidirectional"))
    )
    (net (code "55") (name "VUSB") (class "Default")
      (node (ref "C1") (pin "2") (pinfunction "2_2") (pintype "passive"))
      (node (ref "F2") (pin "2") (pinfunction "2_2") (pintype "bidirectional"))
      (node (ref "R9") (pin "1") (pinfunction "1_1") (pintype "passive"))
      (node (ref "U3") (pin "1") (pinfunction "VIN_1") (pintype "input"))
    )
    (net (code "56") (name "unconnected-(U3-NC-Pad4)") (class "Default")
      (node (ref "U3") (pin "4") (pinfunction "NC_4") (pintype "no_connect"))
    )
    (net (code "57") (name "unconnected-(U4-PA02(AIN0{slash}DAC)-Pad3)") (class "Default")
      (node (ref "U4") (pin "3") (pinfunction "PA02(AIN0/DAC)_3") (pintype "bidirectional"))
    )
    (net (code "58") (name "unconnected-(U4-PA03(AIN1{slash}REFA)-Pad4)") (class "Default")
      (node (ref "U4") (pin "4") (pinfunction "PA03(AIN1/REFA)_4") (pintype "bidirectional"))
    )
    (net (code "59") (name "unconnected-(U4-PA14(XIN{slash}SER2:2+)-Pad23)") (class "Default")
      (node (ref "U4") (pin "23") (pinfunction "PA14(XIN/SER2:2+)_23") (pintype "bidirectional"))
    )
    (net (code "60") (name "unconnected-(U4-PA15(XOUT{slash}SER2:3+)-Pad24)") (class "Default")
      (node (ref "U4") (pin "24") (pinfunction "PA15(XOUT/SER2:3+)_24") (pintype "bidirectional"))
    )
    (net (code "61") (name "unconnected-(U4-PB02(AIN10{slash}SER5:0)-Pad47)") (class "Default")
      (node (ref "U4") (pin "47") (pinfunction "PB02(AIN10/SER5:0)_47") (pintype "bidirectional"))
    )
    (net (code "62") (name "unconnected-(U9-DIO3-PadB6)") (class "Default")
      (node (ref "U9") (pin "B6") (pinfunction "DIO3_B6") (pintype "bidirectional"))
    )
    (net (code "63") (name "unconnected-(U9-DIO4-PadB5)") (class "Default")
      (node (ref "U9") (pin "B5") (pinfunction "DIO4_B5") (pintype "bidirectional"))
    )
    (net (code "64") (name "unconnected-(U9-DIO5-PadA7)") (class "Default")
      (node (ref "U9") (pin "A7") (pinfunction "DIO5_A7") (pintype "bidirectional"))
    )
    (net (code "65") (name "unconnected-(USB1-ID-Pad4)") (class "Default")
      (node (ref "USB1") (pin "4") (pinfunction "ID_4") (pintype "bidirectional"))
    )
  )
)
